# Obscurum-MB_1a.net
KiCad netlist of a schematic drawn in Altium Designer
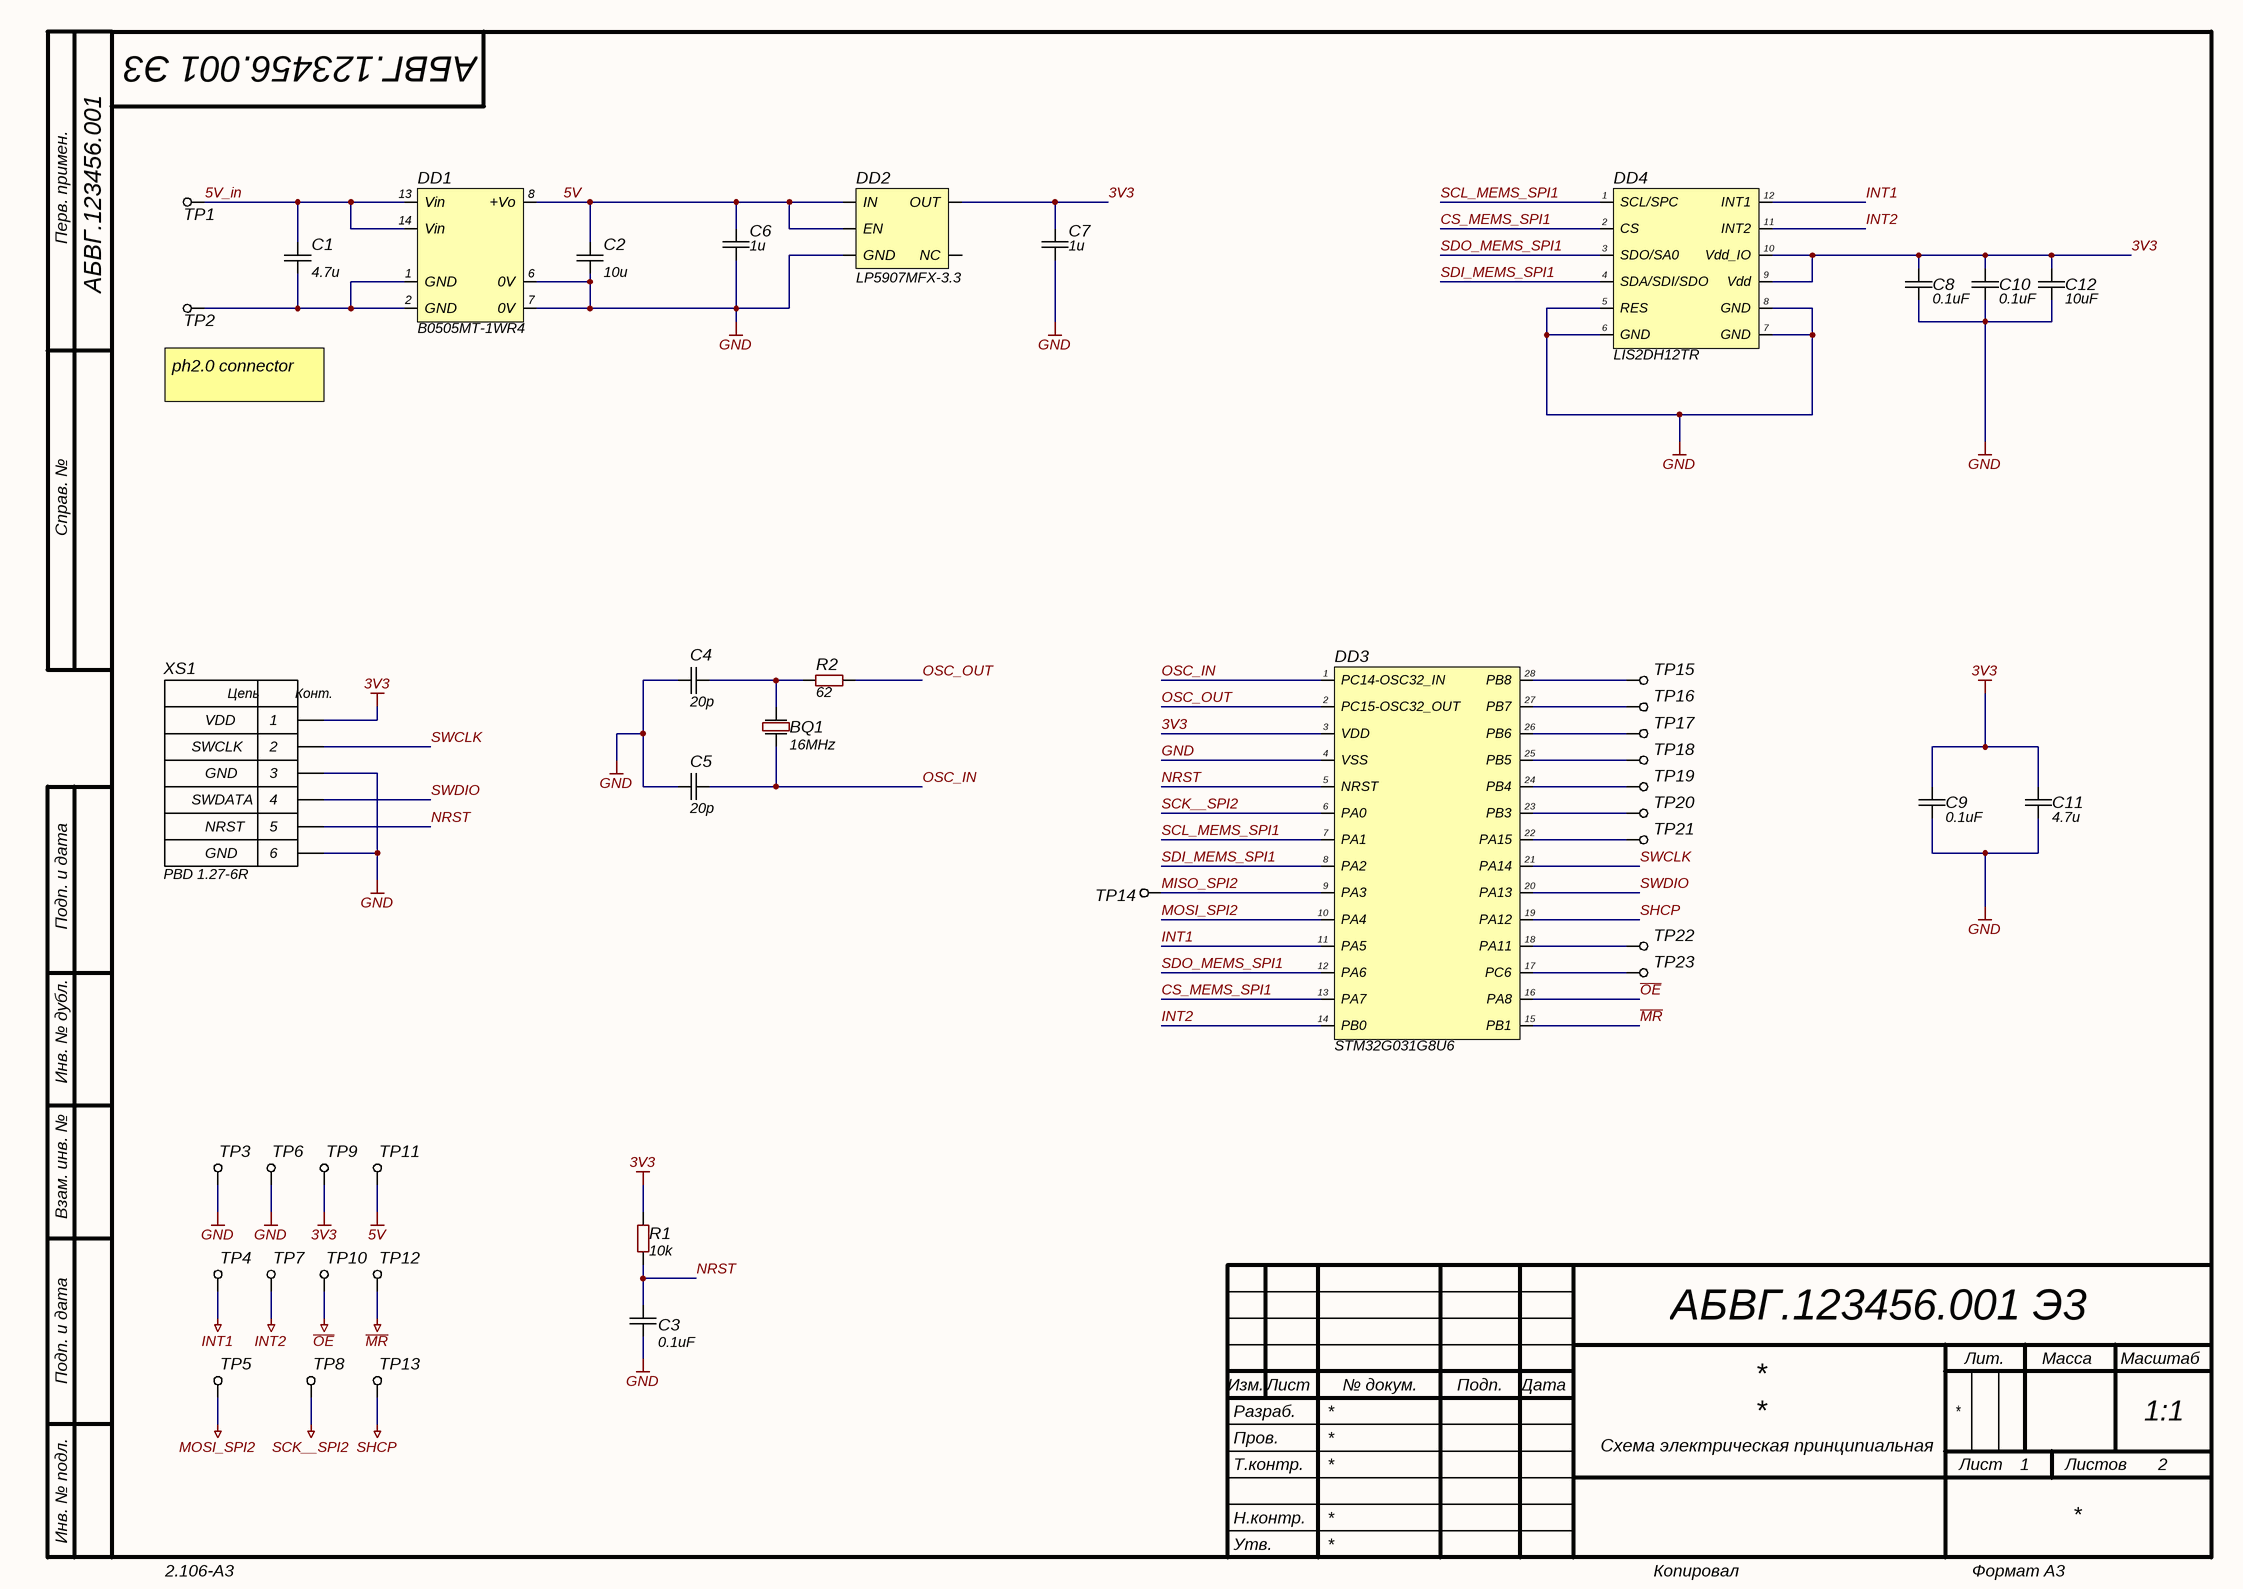
[diagram p0: Obscurum-MB_1a.SchDoc]

(export (version "E")
  (design (tool "Eeschema 10.0.6"))
  (components
    (comp (ref "BQ1")
      (value "SMD3225-16.000MHz")
      (footprint "OSC: 3225")
      (description "Resonator")
      (fields
        (field (name "MANUFACTURER") "Diodes Incorporated")
        (field (name "PARTNUMBER") "FL1000002")
        (field (name "FREQUENCY") "16MHz")
      )
      (libsource (lib "oscilator") (part "Crystal_3225"))
    )
    (comp (ref "C1")
      (value "4.7u")
      (footprint "CAP: 0805")
      (fields
        (field (name "MANUFACTURER") "Yageo")
        (field (name "PARTNUMBER") "CC0805KRX7R7BB104")
        (field (name "VALUEMANUFACTURERPARTNUMBER") "Ceramic capacitor, 4.7u, X7R, ±10%, 50V, 0805, -55...+125°C")
      )
      (libsource (lib "capacitor") (part "Ceramic_0805"))
    )
    (comp (ref "C2")
      (value "10u")
      (footprint "CAP: 0805")
      (fields
        (field (name "MANUFACTURER") "Yageo")
        (field (name "PARTNUMBER") "CC0805KRX7R7BB104")
        (field (name "VALUEMANUFACTURERPARTNUMBER") "Ceramic capacitor, 10u, X7R, ±10%, 50V, 0805, -55...+125°C")
      )
      (libsource (lib "capacitor") (part "Ceramic_0805"))
    )
    (comp (ref "C3")
      (value "0.1uF")
      (footprint "CAP: 0603")
      (fields
        (field (name "MANUFACTURER") "Yageo")
        (field (name "PARTNUMBER") "CC0603KRX7R7BB104")
        (field (name "VALUEMANUFACTURERPARTNUMBER") "Ceramic capacitor, 0.1uF, X7R, ±10%, 16V, 0603, -55...+125°C")
      )
      (libsource (lib "capacitor") (part "Ceramic_0603"))
    )
    (comp (ref "C4")
      (value "20p")
      (footprint "CAP: 0603")
      (description "Capacitor")
      (fields (field (name "MANUFACTURER") "Yageo") (field (name "PARTNUMBER") "CC0603KRX7R7BB104"))
      (libsource (lib "capacitor") (part "Ceramic_0603"))
    )
    (comp (ref "C5")
      (value "20p")
      (footprint "CAP: 0603")
      (description "Capacitor")
      (fields (field (name "MANUFACTURER") "Yageo") (field (name "PARTNUMBER") "CC0603KRX7R7BB104"))
      (libsource (lib "capacitor") (part "Ceramic_0603"))
    )
    (comp (ref "C6")
      (value "1u")
      (footprint "CAP: 0603")
      (description "Capacitor")
      (fields (field (name "MANUFACTURER") "Yageo") (field (name "PARTNUMBER") "CC0603KRX7R7BB104"))
      (libsource (lib "capacitor") (part "Ceramic_0603"))
    )
    (comp (ref "C7")
      (value "1u")
      (footprint "CAP: 0603")
      (description "Capacitor")
      (fields (field (name "MANUFACTURER") "Yageo") (field (name "PARTNUMBER") "CC0603KRX7R7BB104"))
      (libsource (lib "capacitor") (part "Ceramic_0603"))
    )
    (comp (ref "C8")
      (value "0.1uF")
      (footprint "CAP: 0603")
      (fields
        (field (name "MANUFACTURER") "Yageo")
        (field (name "PARTNUMBER") "CC0603KRX7R7BB104")
        (field (name "VALUEMANUFACTURERPARTNUMBER") "Ceramic capacitor, 0.1uF, X7R, ±10%, 16V, 0603, -55...+125°C")
      )
      (libsource (lib "capacitor") (part "Ceramic_0603"))
    )
    (comp (ref "C9")
      (value "0.1uF")
      (footprint "CAP: 0603")
      (fields
        (field (name "MANUFACTURER") "Yageo")
        (field (name "PARTNUMBER") "CC0603KRX7R7BB104")
        (field (name "VALUEMANUFACTURERPARTNUMBER") "Ceramic capacitor, 0.1uF, X7R, ±10%, 16V, 0603, -55...+125°C")
      )
      (libsource (lib "capacitor") (part "Ceramic_0603"))
    )
    (comp (ref "C10")
      (value "0.1uF")
      (footprint "CAP: 0603")
      (fields
        (field (name "MANUFACTURER") "Yageo")
        (field (name "PARTNUMBER") "CC0603KRX7R7BB104")
        (field (name "VALUEMANUFACTURERPARTNUMBER") "Ceramic capacitor, 0.1uF, X7R, ±10%, 16V, 0603, -55...+125°C")
      )
      (libsource (lib "capacitor") (part "Ceramic_0603"))
    )
    (comp (ref "C11")
      (value "4.7u")
      (footprint "CAP: 0603")
      (fields
        (field (name "MANUFACTURER") "Yageo")
        (field (name "PARTNUMBER") "CC0603KRX7R7BB104")
        (field (name "VALUEMANUFACTURERPARTNUMBER") "Ceramic capacitor, 4.7u, X7R, ±10%, 16V, 0603, -55...+125°C")
      )
      (libsource (lib "capacitor") (part "Ceramic_0603"))
    )
    (comp (ref "C12")
      (value "10uF")
      (footprint "CAP: 0603")
      (fields
        (field (name "MANUFACTURER") "Yageo")
        (field (name "PARTNUMBER") "CC0603KRX7R7BB104")
        (field (name "VALUEMANUFACTURERPARTNUMBER") "Ceramic capacitor, 10uF, X7R, ±10%, 16V, 0603, -55...+125°C")
      )
      (libsource (lib "capacitor") (part "Ceramic_0603"))
    )
    (comp (ref "DD1")
      (value "B0505MT-1WR4")
      (footprint "B0505MT-1WR4")
      (description "Isolated DC-DC converter")
      (libsource (lib "ic-power-supply") (part "B0505MT-1WR4"))
    )
    (comp (ref "DD2")
      (value "LP5907MFX-3.3")
      (footprint "SOT23-5")
      (description "LDO")
      (libsource (lib "ic-power-supply") (part "LP5907MFX-3.3"))
    )
    (comp (ref "DD3")
      (value "STM32G031G8U6")
      (footprint "28-UFQFPN")
      (description "Cortex-M0+")
      (libsource (lib "ic-mcu") (part "STM32G031G8U6"))
    )
    (comp (ref "DD4")
      (value "LIS2DH12TR")
      (footprint "12-LGA")
      (description "MEMS accelerometer")
      (libsource (lib "electromechanics") (part "LIS2DH12TR"))
    )
    (comp (ref "R1")
      (value "10k")
      (footprint "RES: 0603")
      (fields
        (field (name "MANUFACTURER") "Yageo")
        (field (name "PARTNUMBER") "RC0603JR-07100RL")
        (field (name "VALUEMANUFACTURERPARTNUMBER") "Resistor film, 10k, , 0603, 0.1W, -55...+125°C")
      )
      (libsource (lib "") (part "Resistor_0603_1"))
    )
    (comp (ref "R2")
      (value "62")
      (footprint "RES: 0603")
      (description "Resistor")
      (fields (field (name "MANUFACTURER") "Yageo") (field (name "PARTNUMBER") "RC0603JR-07100RL"))
      (libsource (lib "resistor") (part "Resistor_0603"))
    )
    (comp (ref "TP1")
      (value "Testpoint_HS1mm")
      (footprint "TestPoint(without 3D)")
      (libsource (lib "connector") (part "Testpoint_HS1mm"))
    )
    (comp (ref "TP2")
      (value "Testpoint_HS1mm")
      (footprint "TestPoint(without 3D)")
      (libsource (lib "connector") (part "Testpoint_HS1mm"))
    )
    (comp (ref "TP3")
      (value "Testpoint_HS1mm")
      (footprint "TestPoint(without hole)")
      (libsource (lib "connector") (part "Testpoint_HS1mm"))
    )
    (comp (ref "TP4")
      (value "Testpoint_HS1mm")
      (footprint "TestPoint(without hole)")
      (libsource (lib "connector") (part "Testpoint_HS1mm"))
    )
    (comp (ref "TP5")
      (value "Testpoint_HS1mm")
      (footprint "TestPoint(without hole)")
      (libsource (lib "connector") (part "Testpoint_HS1mm"))
    )
    (comp (ref "TP6")
      (value "Testpoint_HS1mm")
      (footprint "TestPoint(without hole)")
      (libsource (lib "connector") (part "Testpoint_HS1mm"))
    )
    (comp (ref "TP7")
      (value "Testpoint_HS1mm")
      (footprint "TestPoint(without hole)")
      (libsource (lib "connector") (part "Testpoint_HS1mm"))
    )
    (comp (ref "TP8")
      (value "Testpoint_HS1mm")
      (footprint "TestPoint(without hole)")
      (libsource (lib "connector") (part "Testpoint_HS1mm"))
    )
    (comp (ref "TP9")
      (value "Testpoint_HS1mm")
      (footprint "TestPoint(without hole)")
      (libsource (lib "connector") (part "Testpoint_HS1mm"))
    )
    (comp (ref "TP10")
      (value "Testpoint_HS1mm")
      (footprint "TestPoint(without hole)")
      (libsource (lib "connector") (part "Testpoint_HS1mm"))
    )
    (comp (ref "TP11")
      (value "Testpoint_HS1mm")
      (footprint "TestPoint(without hole)")
      (libsource (lib "connector") (part "Testpoint_HS1mm"))
    )
    (comp (ref "TP12")
      (value "Testpoint_HS1mm")
      (footprint "TestPoint(without hole)")
      (libsource (lib "connector") (part "Testpoint_HS1mm"))
    )
    (comp (ref "TP13")
      (value "Testpoint_HS1mm")
      (footprint "TestPoint(without hole)")
      (libsource (lib "connector") (part "Testpoint_HS1mm"))
    )
    (comp (ref "TP14")
      (value "Testpoint_HS1mm")
      (footprint "TestPoint(without hole)")
      (libsource (lib "connector") (part "Testpoint_HS1mm"))
    )
    (comp (ref "TP15")
      (value "Testpoint_HS1mm")
      (footprint "TestPoint(without hole)")
      (libsource (lib "connector") (part "Testpoint_HS1mm"))
    )
    (comp (ref "TP16")
      (value "Testpoint_HS1mm")
      (footprint "TestPoint(without hole)")
      (libsource (lib "connector") (part "Testpoint_HS1mm"))
    )
    (comp (ref "TP17")
      (value "Testpoint_HS1mm")
      (footprint "TestPoint(without hole)")
      (libsource (lib "connector") (part "Testpoint_HS1mm"))
    )
    (comp (ref "TP18")
      (value "Testpoint_HS1mm")
      (footprint "TestPoint(without hole)")
      (libsource (lib "connector") (part "Testpoint_HS1mm"))
    )
    (comp (ref "TP19")
      (value "Testpoint_HS1mm")
      (footprint "TestPoint(without hole)")
      (libsource (lib "connector") (part "Testpoint_HS1mm"))
    )
    (comp (ref "TP20")
      (value "Testpoint_HS1mm")
      (footprint "TestPoint(without hole)")
      (libsource (lib "connector") (part "Testpoint_HS1mm"))
    )
    (comp (ref "TP21")
      (value "Testpoint_HS1mm")
      (footprint "TestPoint(without hole)")
      (libsource (lib "connector") (part "Testpoint_HS1mm"))
    )
    (comp (ref "TP22")
      (value "Testpoint_HS1mm")
      (footprint "TestPoint(without hole)")
      (libsource (lib "connector") (part "Testpoint_HS1mm"))
    )
    (comp (ref "TP23")
      (value "Testpoint_HS1mm")
      (footprint "TestPoint(without hole)")
      (libsource (lib "connector") (part "Testpoint_HS1mm"))
    )
    (comp (ref "XS1")
      (value "PBD 1.27-6R")
      (footprint "CON: PLLD-6R(1.27)")
      (description "DS1065-14-2X3S8BR")
      (libsource (lib "connector") (part "PBD 1.27-6R"))
    )
  )
  (nets
    (net (code "1") (name "/5V_in") (class "Default")
      (node (ref "C1") (pin "2") (pinfunction "2_2") (pintype "passive"))
      (node (ref "DD1") (pin "13") (pinfunction "Vin_13") (pintype "passive"))
      (node (ref "DD1") (pin "14") (pinfunction "Vin_14") (pintype "passive"))
      (node (ref "TP1") (pin "1") (pinfunction "1_1") (pintype "passive"))
    )
    (net (code "2") (name "/CS_MEMS_SPI1") (class "Default")
      (node (ref "DD3") (pin "13") (pinfunction "PA7_13") (pintype "passive"))
      (node (ref "DD4") (pin "2") (pinfunction "CS_2") (pintype "passive"))
    )
    (net (code "3") (name "/MISO_SPI2") (class "Default")
      (node (ref "DD3") (pin "9") (pinfunction "PA3_9") (pintype "passive"))
      (node (ref "TP14") (pin "1") (pinfunction "1_1") (pintype "passive"))
    )
    (net (code "4") (name "/NRST") (class "Default")
      (node (ref "C3") (pin "2") (pinfunction "2_2") (pintype "passive"))
      (node (ref "DD3") (pin "5") (pinfunction "NRST_5") (pintype "passive"))
      (node (ref "R1") (pin "1") (pinfunction "1_1") (pintype "passive"))
      (node (ref "XS1") (pin "5") (pinfunction "5_5") (pintype "passive"))
    )
    (net (code "5") (name "/OSC_IN") (class "Default")
      (node (ref "BQ1") (pin "1") (pinfunction "1_1") (pintype "passive"))
      (node (ref "C5") (pin "1") (pinfunction "1_1") (pintype "passive"))
      (node (ref "DD3") (pin "1") (pinfunction "PC14-OSC32_IN_1") (pintype "passive"))
    )
    (net (code "6") (name "/OSC_OUT") (class "Default")
      (node (ref "DD3") (pin "2") (pinfunction "PC15-OSC32_OUT_2") (pintype "passive"))
      (node (ref "R2") (pin "1") (pinfunction "1_1") (pintype "passive"))
    )
    (net (code "7") (name "/SCL_MEMS_SPI1") (class "Default")
      (node (ref "DD3") (pin "7") (pinfunction "PA1_7") (pintype "passive"))
      (node (ref "DD4") (pin "1") (pinfunction "SCL/SPC_1") (pintype "passive"))
    )
    (net (code "8") (name "/SDI_MEMS_SPI1") (class "Default")
      (node (ref "DD3") (pin "8") (pinfunction "PA2_8") (pintype "passive"))
      (node (ref "DD4") (pin "4") (pinfunction "SDA/SDI/SDO_4") (pintype "passive"))
    )
    (net (code "9") (name "/SDO_MEMS_SPI1") (class "Default")
      (node (ref "DD3") (pin "12") (pinfunction "PA6_12") (pintype "passive"))
      (node (ref "DD4") (pin "3") (pinfunction "SDO/SA0_3") (pintype "passive"))
    )
    (net (code "10") (name "/SWCLK") (class "Default")
      (node (ref "DD3") (pin "21") (pinfunction "PA14_21") (pintype "passive"))
      (node (ref "XS1") (pin "2") (pinfunction "2_2") (pintype "passive"))
    )
    (net (code "11") (name "/SWDIO") (class "Default")
      (node (ref "DD3") (pin "20") (pinfunction "PA13_20") (pintype "passive"))
      (node (ref "XS1") (pin "4") (pinfunction "4_4") (pintype "passive"))
    )
    (net (code "12") (name "3V3") (class "Default")
      (node (ref "C10") (pin "2") (pinfunction "2_2") (pintype "passive"))
      (node (ref "C11") (pin "2") (pinfunction "2_2") (pintype "passive"))
      (node (ref "C12") (pin "2") (pinfunction "2_2") (pintype "passive"))
      (node (ref "C7") (pin "2") (pinfunction "2_2") (pintype "passive"))
      (node (ref "C8") (pin "2") (pinfunction "2_2") (pintype "passive"))
      (node (ref "C9") (pin "2") (pinfunction "2_2") (pintype "passive"))
      (node (ref "DD2") (pin "5") (pinfunction "OUT_5") (pintype "passive"))
      (node (ref "DD3") (pin "3") (pinfunction "VDD_3") (pintype "passive"))
      (node (ref "DD4") (pin "10") (pinfunction "Vdd_IO_10") (pintype "passive"))
      (node (ref "DD4") (pin "9") (pinfunction "Vdd_9") (pintype "passive"))
      (node (ref "R1") (pin "2") (pinfunction "2_2") (pintype "passive"))
      (node (ref "TP9") (pin "1") (pinfunction "1_1") (pintype "passive"))
      (node (ref "XS1") (pin "1") (pinfunction "1_1") (pintype "passive"))
    )
    (net (code "13") (name "5V") (class "Default")
      (node (ref "C2") (pin "2") (pinfunction "2_2") (pintype "passive"))
      (node (ref "C6") (pin "2") (pinfunction "2_2") (pintype "passive"))
      (node (ref "DD1") (pin "8") (pinfunction "+Vo_8") (pintype "passive"))
      (node (ref "DD2") (pin "1") (pinfunction "IN_1") (pintype "passive"))
      (node (ref "DD2") (pin "3") (pinfunction "EN_3") (pintype "passive"))
      (node (ref "TP11") (pin "1") (pinfunction "1_1") (pintype "passive"))
    )
    (net (code "14") (name "GND") (class "Default")
      (node (ref "C10") (pin "1") (pinfunction "1_1") (pintype "passive"))
      (node (ref "C11") (pin "1") (pinfunction "1_1") (pintype "passive"))
      (node (ref "C12") (pin "1") (pinfunction "1_1") (pintype "passive"))
      (node (ref "C2") (pin "1") (pinfunction "1_1") (pintype "passive"))
      (node (ref "C3") (pin "1") (pinfunction "1_1") (pintype "passive"))
      (node (ref "C4") (pin "2") (pinfunction "2_2") (pintype "passive"))
      (node (ref "C5") (pin "2") (pinfunction "2_2") (pintype "passive"))
      (node (ref "C6") (pin "1") (pinfunction "1_1") (pintype "passive"))
      (node (ref "C7") (pin "1") (pinfunction "1_1") (pintype "passive"))
      (node (ref "C8") (pin "1") (pinfunction "1_1") (pintype "passive"))
      (node (ref "C9") (pin "1") (pinfunction "1_1") (pintype "passive"))
      (node (ref "DD1") (pin "6") (pinfunction "0V_6") (pintype "passive"))
      (node (ref "DD1") (pin "7") (pinfunction "0V_7") (pintype "passive"))
      (node (ref "DD2") (pin "2") (pinfunction "GND_2") (pintype "passive"))
      (node (ref "DD3") (pin "4") (pinfunction "VSS_4") (pintype "passive"))
      (node (ref "DD4") (pin "5") (pinfunction "RES_5") (pintype "passive"))
      (node (ref "DD4") (pin "6") (pinfunction "GND_6") (pintype "passive"))
      (node (ref "DD4") (pin "7") (pinfunction "GND_7") (pintype "passive"))
      (node (ref "DD4") (pin "8") (pinfunction "GND_8") (pintype "passive"))
      (node (ref "TP3") (pin "1") (pinfunction "1_1") (pintype "passive"))
      (node (ref "TP6") (pin "1") (pinfunction "1_1") (pintype "passive"))
      (node (ref "XS1") (pin "3") (pinfunction "3_3") (pintype "passive"))
      (node (ref "XS1") (pin "6") (pinfunction "6_6") (pintype "passive"))
    )
    (net (code "15") (name "INT1") (class "Default")
      (node (ref "DD3") (pin "11") (pinfunction "PA5_11") (pintype "passive"))
      (node (ref "DD4") (pin "12") (pinfunction "INT1_12") (pintype "passive"))
      (node (ref "TP4") (pin "1") (pinfunction "1_1") (pintype "passive"))
    )
    (net (code "16") (name "INT2") (class "Default")
      (node (ref "DD3") (pin "14") (pinfunction "PB0_14") (pintype "passive"))
      (node (ref "DD4") (pin "11") (pinfunction "INT2_11") (pintype "passive"))
      (node (ref "TP7") (pin "1") (pinfunction "1_1") (pintype "passive"))
    )
    (net (code "17") (name "MOSI_SPI2") (class "Default")
      (node (ref "DD3") (pin "10") (pinfunction "PA4_10") (pintype "passive"))
      (node (ref "TP5") (pin "1") (pinfunction "1_1") (pintype "passive"))
    )
    (net (code "18") (name "Net-(BQ1-Pad3)") (class "Default")
      (node (ref "BQ1") (pin "3") (pinfunction "3_3") (pintype "passive"))
      (node (ref "C4") (pin "1") (pinfunction "1_1") (pintype "passive"))
      (node (ref "R2") (pin "2") (pinfunction "2_2") (pintype "passive"))
    )
    (net (code "19") (name "Net-(C1-Pad1)") (class "Default")
      (node (ref "C1") (pin "1") (pinfunction "1_1") (pintype "passive"))
      (node (ref "DD1") (pin "1") (pinfunction "GND_1") (pintype "passive"))
      (node (ref "DD1") (pin "2") (pinfunction "GND_2") (pintype "passive"))
      (node (ref "TP2") (pin "1") (pinfunction "1_1") (pintype "passive"))
    )
    (net (code "20") (name "Net-(DD3-PA11)") (class "Default")
      (node (ref "DD3") (pin "18") (pinfunction "PA11_18") (pintype "passive"))
      (node (ref "TP22") (pin "1") (pinfunction "1_1") (pintype "passive"))
    )
    (net (code "21") (name "Net-(DD3-PA15)") (class "Default")
      (node (ref "DD3") (pin "22") (pinfunction "PA15_22") (pintype "passive"))
      (node (ref "TP21") (pin "1") (pinfunction "1_1") (pintype "passive"))
    )
    (net (code "22") (name "Net-(DD3-PB3)") (class "Default")
      (node (ref "DD3") (pin "23") (pinfunction "PB3_23") (pintype "passive"))
      (node (ref "TP20") (pin "1") (pinfunction "1_1") (pintype "passive"))
    )
    (net (code "23") (name "Net-(DD3-PB4)") (class "Default")
      (node (ref "DD3") (pin "24") (pinfunction "PB4_24") (pintype "passive"))
      (node (ref "TP19") (pin "1") (pinfunction "1_1") (pintype "passive"))
    )
    (net (code "24") (name "Net-(DD3-PB5)") (class "Default")
      (node (ref "DD3") (pin "25") (pinfunction "PB5_25") (pintype "passive"))
      (node (ref "TP18") (pin "1") (pinfunction "1_1") (pintype "passive"))
    )
    (net (code "25") (name "Net-(DD3-PB6)") (class "Default")
      (node (ref "DD3") (pin "26") (pinfunction "PB6_26") (pintype "passive"))
      (node (ref "TP17") (pin "1") (pinfunction "1_1") (pintype "passive"))
    )
    (net (code "26") (name "Net-(DD3-PB7)") (class "Default")
      (node (ref "DD3") (pin "27") (pinfunction "PB7_27") (pintype "passive"))
      (node (ref "TP16") (pin "1") (pinfunction "1_1") (pintype "passive"))
    )
    (net (code "27") (name "Net-(DD3-PB8)") (class "Default")
      (node (ref "DD3") (pin "28") (pinfunction "PB8_28") (pintype "passive"))
      (node (ref "TP15") (pin "1") (pinfunction "1_1") (pintype "passive"))
    )
    (net (code "28") (name "Net-(DD3-PC6)") (class "Default")
      (node (ref "DD3") (pin "17") (pinfunction "PC6_17") (pintype "passive"))
      (node (ref "TP23") (pin "1") (pinfunction "1_1") (pintype "passive"))
    )
    (net (code "29") (name "SCK__SPI2") (class "Default")
      (node (ref "DD3") (pin "6") (pinfunction "PA0_6") (pintype "passive"))
      (node (ref "TP8") (pin "1") (pinfunction "1_1") (pintype "passive"))
    )
    (net (code "30") (name "SHCP") (class "Default")
      (node (ref "DD3") (pin "19") (pinfunction "PA12_19") (pintype "passive"))
      (node (ref "TP13") (pin "1") (pinfunction "1_1") (pintype "passive"))
    )
    (net (code "31") (name "unconnected-(DD2-NC-Pad4)") (class "Default")
      (node (ref "DD2") (pin "4") (pinfunction "NC_4") (pintype "passive"))
    )
    (net (code "32") (name "~{MR}") (class "Default")
      (node (ref "DD3") (pin "15") (pinfunction "PB1_15") (pintype "passive"))
      (node (ref "TP12") (pin "1") (pinfunction "1_1") (pintype "passive"))
    )
    (net (code "33") (name "~{OE}") (class "Default")
      (node (ref "DD3") (pin "16") (pinfunction "PA8_16") (pintype "passive"))
      (node (ref "TP10") (pin "1") (pinfunction "1_1") (pintype "passive"))
    )
  )
)
